# pcb2-1.net
KiCad netlist of a schematic drawn in EAGLE
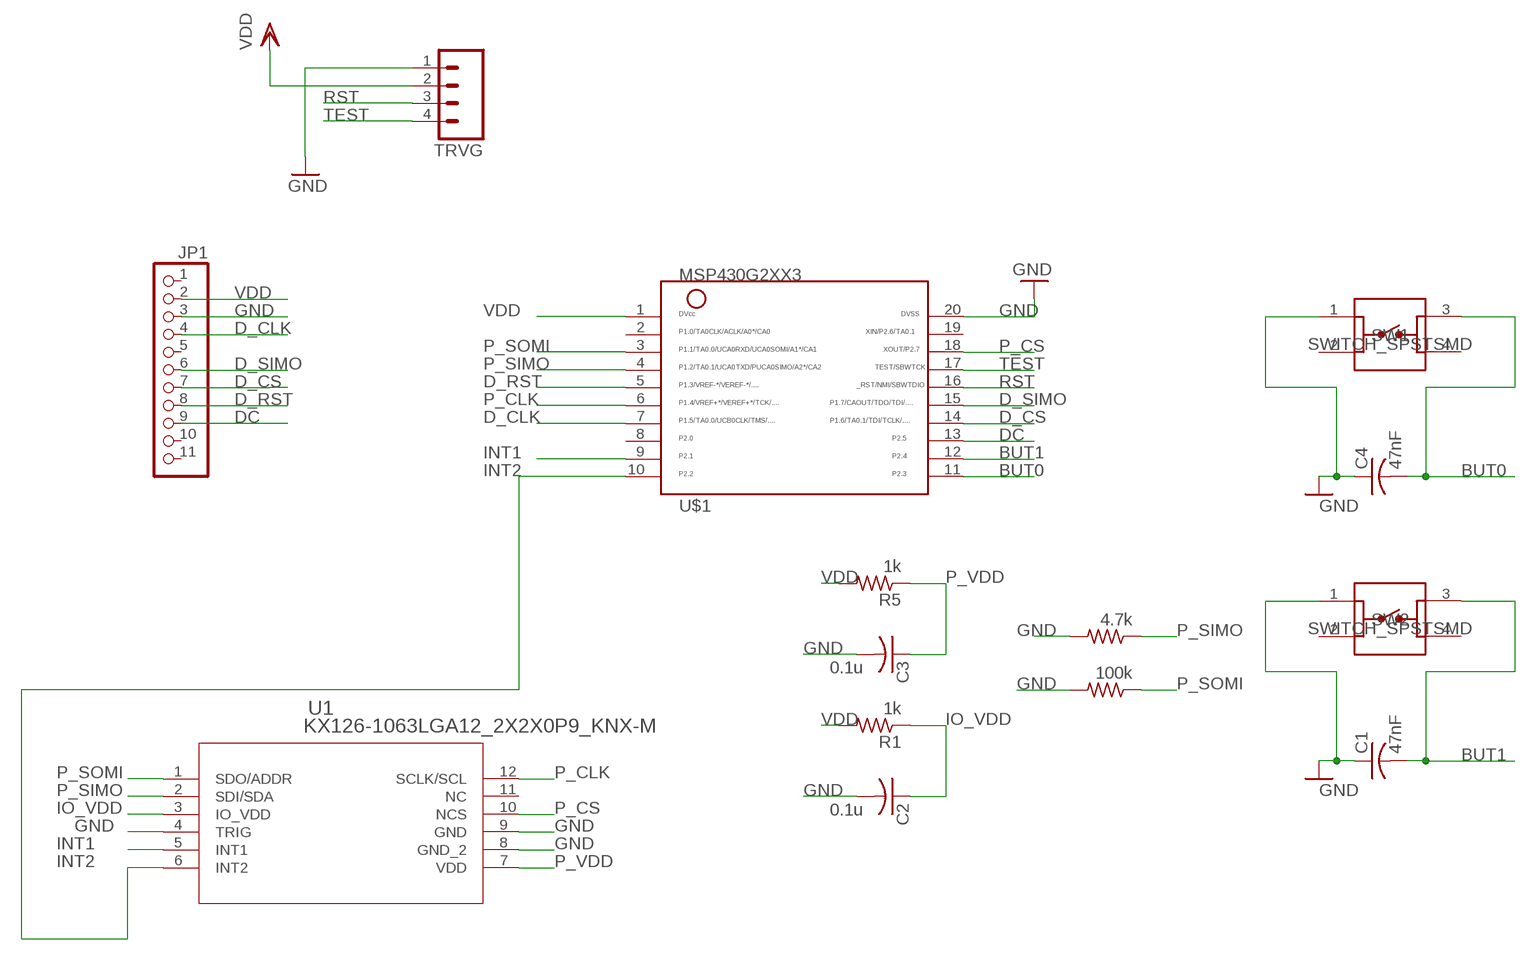
[diagram p0: schematic, sheet 1]

(export (version "E")
  (design (tool "Eeschema 10.0.6"))
  (components
    (comp (ref "C1")
      (value "47nF")
      (footprint "eagle-import:C0603")
      (libsource (lib "eagle-import") (part "C-USC0603"))
    )
    (comp (ref "C2")
      (value "0.1u")
      (footprint "eagle-import:C0603")
      (libsource (lib "eagle-import") (part "C-USC0603"))
    )
    (comp (ref "C3")
      (value "0.1u")
      (footprint "eagle-import:C0603")
      (libsource (lib "eagle-import") (part "C-USC0603"))
    )
    (comp (ref "C4")
      (value "47nF")
      (footprint "eagle-import:C0603")
      (libsource (lib "eagle-import") (part "C-USC0603"))
    )
    (comp (ref "JP1")
      (value "HEADER-1X11")
      (footprint "eagle-import:1X11_ROUND")
      (libsource (lib "eagle-import") (part "HEADER-1X11"))
    )
    (comp (ref "R1")
      (value "1k")
      (footprint "eagle-import:R0402")
      (libsource (lib "eagle-import") (part "R-US_R0402"))
    )
    (comp (ref "R2")
      (value "100k")
      (footprint "eagle-import:R0402")
      (libsource (lib "eagle-import") (part "R-US_R0402"))
    )
    (comp (ref "R3")
      (value "4.7k")
      (footprint "eagle-import:R0402")
      (libsource (lib "eagle-import") (part "R-US_R0402"))
    )
    (comp (ref "R5")
      (value "1k")
      (footprint "eagle-import:R0402")
      (libsource (lib "eagle-import") (part "R-US_R0402"))
    )
    (comp (ref "SW1")
      (value "SWITCH_SPSTSMD")
      (footprint "eagle-import:SW_1571563-4")
      (libsource (lib "eagle-import") (part "SWITCH_SPSTSMD"))
    )
    (comp (ref "SW2")
      (value "SWITCH_SPSTSMD")
      (footprint "eagle-import:SW_1571563-4")
      (libsource (lib "eagle-import") (part "SWITCH_SPSTSMD"))
    )
    (comp (ref "TRVG")
      (value "M04LOCK")
      (footprint "eagle-import:1X04_LOCK")
      (libsource (lib "eagle-import") (part "M04LOCK"))
    )
    (comp (ref "U$1")
      (value "MSP430G2XX3TSSOP")
      (footprint "eagle-import:PW20")
      (libsource (lib "eagle-import") (part "MSP430G2XX3TSSOP"))
    )
    (comp (ref "U1")
      (value "KX126-1063LGA12_2X2X0P9_KNX-M")
      (footprint "eagle-import:LGA12_2X2X0P9_KNX-M")
      (fields
        (field (name "MANUFACTURER_PART_NUMBER") "KX126-1063")
        (field (name "COPYRIGHT") "Copyright (C) 2021 Ultra Librarian. All rights reserved.")
      )
      (libsource (lib "eagle-import") (part "KX126-1063LGA12_2X2X0P9_KNX-M"))
    )
  )
  (nets
    (net (code "1") (name "/BUT0") (class "Default")
      (node (ref "C4") (pin "2") (pinfunction "2_2") (pintype "passive"))
      (node (ref "SW1") (pin "3") (pinfunction "3_3") (pintype "passive"))
      (node (ref "U$1") (pin "11") (pinfunction "11_11") (pintype "bidirectional"))
    )
    (net (code "2") (name "/BUT1") (class "Default")
      (node (ref "C1") (pin "2") (pinfunction "2_2") (pintype "passive"))
      (node (ref "SW2") (pin "3") (pinfunction "3_3") (pintype "passive"))
      (node (ref "U$1") (pin "12") (pinfunction "12_12") (pintype "bidirectional"))
    )
    (net (code "3") (name "/DC") (class "Default")
      (node (ref "JP1") (pin "9") (pinfunction "9_9") (pintype "passive"))
      (node (ref "U$1") (pin "13") (pinfunction "13_13") (pintype "bidirectional"))
    )
    (net (code "4") (name "/D_CLK") (class "Default")
      (node (ref "JP1") (pin "4") (pinfunction "4_4") (pintype "passive"))
      (node (ref "U$1") (pin "7") (pinfunction "7_7") (pintype "bidirectional"))
    )
    (net (code "5") (name "/D_CS") (class "Default")
      (node (ref "JP1") (pin "7") (pinfunction "7_7") (pintype "passive"))
      (node (ref "U$1") (pin "14") (pinfunction "14_14") (pintype "bidirectional"))
    )
    (net (code "6") (name "/D_RST") (class "Default")
      (node (ref "JP1") (pin "8") (pinfunction "8_8") (pintype "passive"))
      (node (ref "U$1") (pin "5") (pinfunction "5_5") (pintype "bidirectional"))
    )
    (net (code "7") (name "/D_SIMO") (class "Default")
      (node (ref "JP1") (pin "6") (pinfunction "6_6") (pintype "passive"))
      (node (ref "U$1") (pin "15") (pinfunction "15_15") (pintype "bidirectional"))
    )
    (net (code "8") (name "/INT1") (class "Default")
      (node (ref "U$1") (pin "9") (pinfunction "9_9") (pintype "bidirectional"))
      (node (ref "U1") (pin "5") (pinfunction "INT1_5") (pintype "output"))
    )
    (net (code "9") (name "/INT2") (class "Default")
      (node (ref "U$1") (pin "10") (pinfunction "10_10") (pintype "bidirectional"))
      (node (ref "U1") (pin "6") (pinfunction "INT2_6") (pintype "output"))
    )
    (net (code "10") (name "/IO_VDD") (class "Default")
      (node (ref "C2") (pin "1") (pinfunction "1_1") (pintype "passive"))
      (node (ref "R1") (pin "1") (pinfunction "1_1") (pintype "passive"))
      (node (ref "U1") (pin "3") (pinfunction "IO_VDD_3") (pintype "power_in"))
    )
    (net (code "11") (name "/P_CLK") (class "Default")
      (node (ref "U$1") (pin "6") (pinfunction "6_6") (pintype "bidirectional"))
      (node (ref "U1") (pin "12") (pinfunction "SCLK/SCL_12") (pintype "input"))
    )
    (net (code "12") (name "/P_CS") (class "Default")
      (node (ref "U$1") (pin "18") (pinfunction "18_18") (pintype "bidirectional"))
      (node (ref "U1") (pin "10") (pinfunction "NCS_10") (pintype "input"))
    )
    (net (code "13") (name "/P_SIMO") (class "Default")
      (node (ref "R3") (pin "1") (pinfunction "1_1") (pintype "passive"))
      (node (ref "U$1") (pin "4") (pinfunction "4_4") (pintype "bidirectional"))
      (node (ref "U1") (pin "2") (pinfunction "SDI/SDA_2") (pintype "input"))
    )
    (net (code "14") (name "/P_SOMI") (class "Default")
      (node (ref "R2") (pin "1") (pinfunction "1_1") (pintype "passive"))
      (node (ref "U$1") (pin "3") (pinfunction "3_3") (pintype "bidirectional"))
      (node (ref "U1") (pin "1") (pinfunction "SDO/ADDR_1") (pintype "input"))
    )
    (net (code "15") (name "/P_VDD") (class "Default")
      (node (ref "C3") (pin "1") (pinfunction "1_1") (pintype "passive"))
      (node (ref "R5") (pin "1") (pinfunction "1_1") (pintype "passive"))
      (node (ref "U1") (pin "7") (pinfunction "VDD_7") (pintype "power_in"))
    )
    (net (code "16") (name "/RST") (class "Default")
      (node (ref "TRVG") (pin "3") (pinfunction "3_3") (pintype "passive"))
      (node (ref "U$1") (pin "16") (pinfunction "16_16") (pintype "bidirectional"))
    )
    (net (code "17") (name "/TEST") (class "Default")
      (node (ref "TRVG") (pin "4") (pinfunction "4_4") (pintype "passive"))
      (node (ref "U$1") (pin "17") (pinfunction "17_17") (pintype "bidirectional"))
    )
    (net (code "18") (name "GND") (class "Default")
      (node (ref "C1") (pin "1") (pinfunction "1_1") (pintype "passive"))
      (node (ref "C2") (pin "2") (pinfunction "2_2") (pintype "passive"))
      (node (ref "C3") (pin "2") (pinfunction "2_2") (pintype "passive"))
      (node (ref "C4") (pin "1") (pinfunction "1_1") (pintype "passive"))
      (node (ref "JP1") (pin "3") (pinfunction "3_3") (pintype "passive"))
      (node (ref "R2") (pin "2") (pinfunction "2_2") (pintype "passive"))
      (node (ref "R3") (pin "2") (pinfunction "2_2") (pintype "passive"))
      (node (ref "SW1") (pin "1") (pinfunction "1_1") (pintype "passive"))
      (node (ref "SW2") (pin "1") (pinfunction "1_1") (pintype "passive"))
      (node (ref "TRVG") (pin "1") (pinfunction "1_1") (pintype "passive"))
      (node (ref "U$1") (pin "20") (pinfunction "20_20") (pintype "bidirectional"))
      (node (ref "U1") (pin "4") (pinfunction "TRIG_4") (pintype "input"))
      (node (ref "U1") (pin "8") (pinfunction "GND_2_8") (pintype "passive"))
      (node (ref "U1") (pin "9") (pinfunction "GND_9") (pintype "passive"))
    )
    (net (code "19") (name "VDD") (class "Default")
      (node (ref "JP1") (pin "2") (pinfunction "2_2") (pintype "passive"))
      (node (ref "R1") (pin "2") (pinfunction "2_2") (pintype "passive"))
      (node (ref "R5") (pin "2") (pinfunction "2_2") (pintype "passive"))
      (node (ref "TRVG") (pin "2") (pinfunction "2_2") (pintype "passive"))
      (node (ref "U$1") (pin "1") (pinfunction "1_1") (pintype "bidirectional"))
    )
    (net (code "20") (name "unconnected-(JP1-Pad1)") (class "Default")
      (node (ref "JP1") (pin "1") (pinfunction "1_1") (pintype "passive"))
    )
    (net (code "21") (name "unconnected-(JP1-Pad5)") (class "Default")
      (node (ref "JP1") (pin "5") (pinfunction "5_5") (pintype "passive"))
    )
    (net (code "22") (name "unconnected-(JP1-Pad10)") (class "Default")
      (node (ref "JP1") (pin "10") (pinfunction "10_10") (pintype "passive"))
    )
    (net (code "23") (name "unconnected-(JP1-Pad11)") (class "Default")
      (node (ref "JP1") (pin "11") (pinfunction "11_11") (pintype "passive"))
    )
    (net (code "24") (name "unconnected-(SW1-Pad2)") (class "Default")
      (node (ref "SW1") (pin "2") (pinfunction "2_2") (pintype "passive"))
    )
    (net (code "25") (name "unconnected-(SW1-Pad4)") (class "Default")
      (node (ref "SW1") (pin "4") (pinfunction "4_4") (pintype "passive"))
    )
    (net (code "26") (name "unconnected-(SW2-Pad2)") (class "Default")
      (node (ref "SW2") (pin "2") (pinfunction "2_2") (pintype "passive"))
    )
    (net (code "27") (name "unconnected-(SW2-Pad4)") (class "Default")
      (node (ref "SW2") (pin "4") (pinfunction "4_4") (pintype "passive"))
    )
    (net (code "28") (name "unconnected-(U$1-Pad2)") (class "Default")
      (node (ref "U$1") (pin "2") (pinfunction "2_2") (pintype "bidirectional"))
    )
    (net (code "29") (name "unconnected-(U$1-Pad8)") (class "Default")
      (node (ref "U$1") (pin "8") (pinfunction "8_8") (pintype "bidirectional"))
    )
    (net (code "30") (name "unconnected-(U$1-Pad19)") (class "Default")
      (node (ref "U$1") (pin "19") (pinfunction "19_19") (pintype "bidirectional"))
    )
    (net (code "31") (name "unconnected-(U1-NC-Pad11)") (class "Default")
      (node (ref "U1") (pin "11") (pinfunction "NC_11") (pintype "no_connect"))
    )
  )
)
